# Expander2.net
KiCad netlist of a schematic drawn in EAGLE
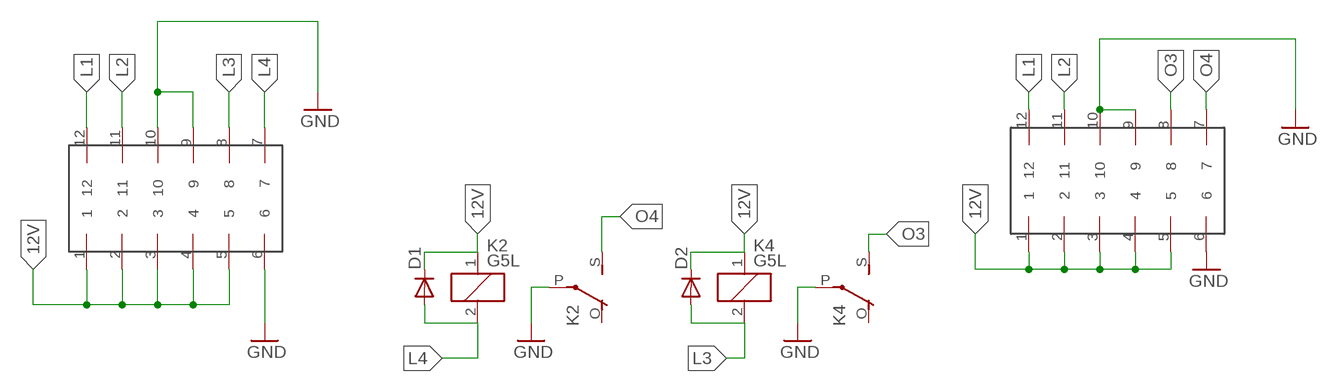
[diagram p0: schematic, sheet 1]

(export (version "E")
  (design (tool "Eeschema 10.0.6"))
  (components
    (comp (ref "D1")
      (value "DIODESMB")
      (footprint "eagle-import:SMB-DIODE")
      (libsource (lib "eagle-import") (part "DIODESMB"))
    )
    (comp (ref "D2")
      (value "DIODESMB")
      (footprint "eagle-import:SMB-DIODE")
      (libsource (lib "eagle-import") (part "DIODESMB"))
    )
    (comp (ref "IN")
      (value "MF42-10")
      (footprint "eagle-import:MF42-10")
      (libsource (lib "eagle-import") (part "MF42-10"))
    )
    (comp (ref "K2")
      (value "G5L")
      (footprint "eagle-import:G5LE")
      (fields (field (name "OC_FARNELL") "unknown") (field (name "OC_NEWARK") "unknown"))
      (libsource (lib "eagle-import") (part "G5L"))
    )
    (comp (ref "K4")
      (value "G5L")
      (footprint "eagle-import:G5LE")
      (fields (field (name "OC_FARNELL") "unknown") (field (name "OC_NEWARK") "unknown"))
      (libsource (lib "eagle-import") (part "G5L"))
    )
    (comp (ref "OUT")
      (value "MF42-10")
      (footprint "eagle-import:MF42-10")
      (libsource (lib "eagle-import") (part "MF42-10"))
    )
  )
  (nets
    (net (code "1") (name "12V") (class "Default")
      (node (ref "D1") (pin "C") (pinfunction "C_C") (pintype "passive"))
      (node (ref "D2") (pin "C") (pinfunction "C_C") (pintype "passive"))
      (node (ref "IN") (pin "1") (pinfunction "1_1") (pintype "bidirectional"))
      (node (ref "IN") (pin "2") (pinfunction "2_2") (pintype "bidirectional"))
      (node (ref "IN") (pin "3") (pinfunction "3_3") (pintype "bidirectional"))
      (node (ref "IN") (pin "4") (pinfunction "4_4") (pintype "bidirectional"))
      (node (ref "IN") (pin "5") (pinfunction "5_5") (pintype "bidirectional"))
      (node (ref "K2") (pin "1") (pinfunction "1_1") (pintype "passive"))
      (node (ref "K4") (pin "1") (pinfunction "1_1") (pintype "passive"))
      (node (ref "OUT") (pin "1") (pinfunction "1_1") (pintype "bidirectional"))
      (node (ref "OUT") (pin "2") (pinfunction "2_2") (pintype "bidirectional"))
      (node (ref "OUT") (pin "3") (pinfunction "3_3") (pintype "bidirectional"))
      (node (ref "OUT") (pin "4") (pinfunction "4_4") (pintype "bidirectional"))
      (node (ref "OUT") (pin "5") (pinfunction "5_5") (pintype "bidirectional"))
    )
    (net (code "2") (name "GND") (class "Default")
      (node (ref "IN") (pin "10") (pinfunction "10_10") (pintype "bidirectional"))
      (node (ref "IN") (pin "6") (pinfunction "6_6") (pintype "bidirectional"))
      (node (ref "IN") (pin "9") (pinfunction "9_9") (pintype "bidirectional"))
      (node (ref "K2") (pin "P") (pinfunction "P_P") (pintype "passive"))
      (node (ref "K4") (pin "P") (pinfunction "P_P") (pintype "passive"))
      (node (ref "OUT") (pin "10") (pinfunction "10_10") (pintype "bidirectional"))
      (node (ref "OUT") (pin "6") (pinfunction "6_6") (pintype "bidirectional"))
      (node (ref "OUT") (pin "9") (pinfunction "9_9") (pintype "bidirectional"))
    )
    (net (code "3") (name "L1") (class "Default")
      (node (ref "IN") (pin "12") (pinfunction "12_12") (pintype "bidirectional"))
      (node (ref "OUT") (pin "12") (pinfunction "12_12") (pintype "bidirectional"))
    )
    (net (code "4") (name "L2") (class "Default")
      (node (ref "IN") (pin "11") (pinfunction "11_11") (pintype "bidirectional"))
      (node (ref "OUT") (pin "11") (pinfunction "11_11") (pintype "bidirectional"))
    )
    (net (code "5") (name "L3") (class "Default")
      (node (ref "D2") (pin "A") (pinfunction "A_A") (pintype "passive"))
      (node (ref "IN") (pin "8") (pinfunction "8_8") (pintype "bidirectional"))
      (node (ref "K4") (pin "2") (pinfunction "2_2") (pintype "passive"))
    )
    (net (code "6") (name "L4") (class "Default")
      (node (ref "D1") (pin "A") (pinfunction "A_A") (pintype "passive"))
      (node (ref "IN") (pin "7") (pinfunction "7_7") (pintype "bidirectional"))
      (node (ref "K2") (pin "2") (pinfunction "2_2") (pintype "passive"))
    )
    (net (code "7") (name "O3") (class "Default")
      (node (ref "K4") (pin "S") (pinfunction "S_S") (pintype "passive"))
      (node (ref "OUT") (pin "8") (pinfunction "8_8") (pintype "bidirectional"))
    )
    (net (code "8") (name "O4") (class "Default")
      (node (ref "K2") (pin "S") (pinfunction "S_S") (pintype "passive"))
      (node (ref "OUT") (pin "7") (pinfunction "7_7") (pintype "bidirectional"))
    )
    (net (code "9") (name "unconnected-(K2-PadO)") (class "Default")
      (node (ref "K2") (pin "O") (pinfunction "O_O") (pintype "passive"))
    )
    (net (code "10") (name "unconnected-(K4-PadO)") (class "Default")
      (node (ref "K4") (pin "O") (pinfunction "O_O") (pintype "passive"))
    )
  )
)
